# LC_LPF5.net
KiCad netlist of a schematic drawn in Altium Designer
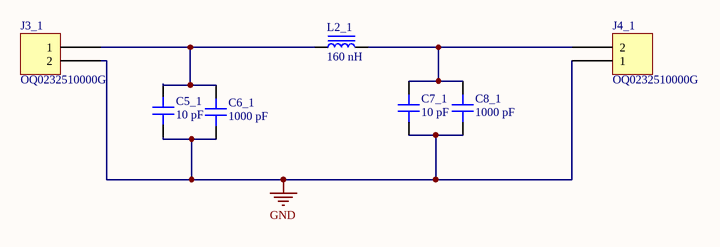
[diagram p0: LC_LPF5.SchDoc]

(export (version "E")
  (design (tool "Eeschema 10.0.6"))
  (components
    (comp (ref "C5_1")
      (value "10 pF")
      (footprint "CAP 0603_1608")
      (description "CAP CER 10PF 100V C0G/NPO 0603")
      (fields (field (name "PART NUMBER") "AC0603JRNPO0BN100") (field (name "MANUFACTURER") "Yageo"))
      (libsource (lib "Celestial Altium Library - altium_library") (part "Capacitor"))
    )
    (comp (ref "C6_1")
      (value "1000 pF")
      (footprint "CAP 0603_1608")
      (description "CAP CER 1000PF 100V X7R 0603")
      (fields
        (field (name "PART NUMBER") "GCD188R72A102KA01D")
        (field (name "MANUFACTURER") "Murata Electronics")
      )
      (libsource (lib "Celestial Altium Library - altium_library") (part "Capacitor"))
    )
    (comp (ref "C7_1")
      (value "10 pF")
      (footprint "CAP 0603_1608")
      (description "CAP CER 10PF 100V C0G/NPO 0603")
      (fields (field (name "PART NUMBER") "AC0603JRNPO0BN100") (field (name "MANUFACTURER") "Yageo"))
      (libsource (lib "Celestial Altium Library - altium_library") (part "Capacitor"))
    )
    (comp (ref "C8_1")
      (value "1000 pF")
      (footprint "CAP 0603_1608")
      (description "CAP CER 1000PF 100V X7R 0603")
      (fields
        (field (name "PART NUMBER") "GCD188R72A102KA01D")
        (field (name "MANUFACTURER") "Murata Electronics")
      )
      (libsource (lib "Celestial Altium Library - altium_library") (part "Capacitor"))
    )
    (comp (ref "J3_1")
      (value "OQ0232510000G")
      (footprint "FCI 06-381-2PIN")
      (description "TERM BLOCK HDR 2POS 90DEG 3.81MM")
      (fields (field (name "MANUFACTURER") "Amphenol Anytek"))
      (libsource (lib "") (part "2 Pin_1"))
    )
    (comp (ref "J4_1")
      (value "OQ0232510000G")
      (footprint "FCI 06-381-2PIN")
      (description "TERM BLOCK HDR 2POS 90DEG 3.81MM")
      (fields (field (name "MANUFACTURER") "Amphenol Anytek"))
      (libsource (lib "Celestial Altium Library - altium_library") (part "2 Pin"))
    )
    (comp (ref "L2_1")
      (value "160 nH")
      (footprint "IND 0402_1005 RF WW")
      (description "FIXED IND 160NH 480MA 330MOHM SM")
      (fields
        (field (name "PART NUMBER") "LQW15CNR16J00D")
        (field (name "MANUFACTURER") "Murata Electronics")
      )
      (libsource (lib "Celestial Altium Library - altium_library") (part "Inductor"))
    )
  )
  (nets
    (net (code "1") (name "GND") (class "Default")
      (node (ref "C5_1") (pin "1") (pinfunction "1_1") (pintype "passive"))
      (node (ref "C6_1") (pin "2") (pinfunction "2_2") (pintype "passive"))
      (node (ref "C7_1") (pin "1") (pinfunction "1_1") (pintype "passive"))
      (node (ref "C8_1") (pin "2") (pinfunction "2_2") (pintype "passive"))
      (node (ref "J3_1") (pin "2") (pinfunction "2_2") (pintype "passive"))
      (node (ref "J4_1") (pin "1") (pinfunction "1_1") (pintype "passive"))
    )
    (net (code "2") (name "Net-(C5_1-Pad2)") (class "Default")
      (node (ref "C5_1") (pin "2") (pinfunction "2_2") (pintype "passive"))
      (node (ref "C6_1") (pin "1") (pinfunction "1_1") (pintype "passive"))
      (node (ref "J3_1") (pin "1") (pinfunction "1_1") (pintype "passive"))
      (node (ref "L2_1") (pin "1") (pinfunction "1_1") (pintype "passive"))
    )
    (net (code "3") (name "Net-(C7_1-Pad2)") (class "Default")
      (node (ref "C7_1") (pin "2") (pinfunction "2_2") (pintype "passive"))
      (node (ref "C8_1") (pin "1") (pinfunction "1_1") (pintype "passive"))
      (node (ref "J4_1") (pin "2") (pinfunction "2_2") (pintype "passive"))
      (node (ref "L2_1") (pin "2") (pinfunction "2_2") (pintype "passive"))
    )
  )
)
